# PunktSchweiss_ohne_NT2.net
KiCad netlist of a schematic drawn in EAGLE
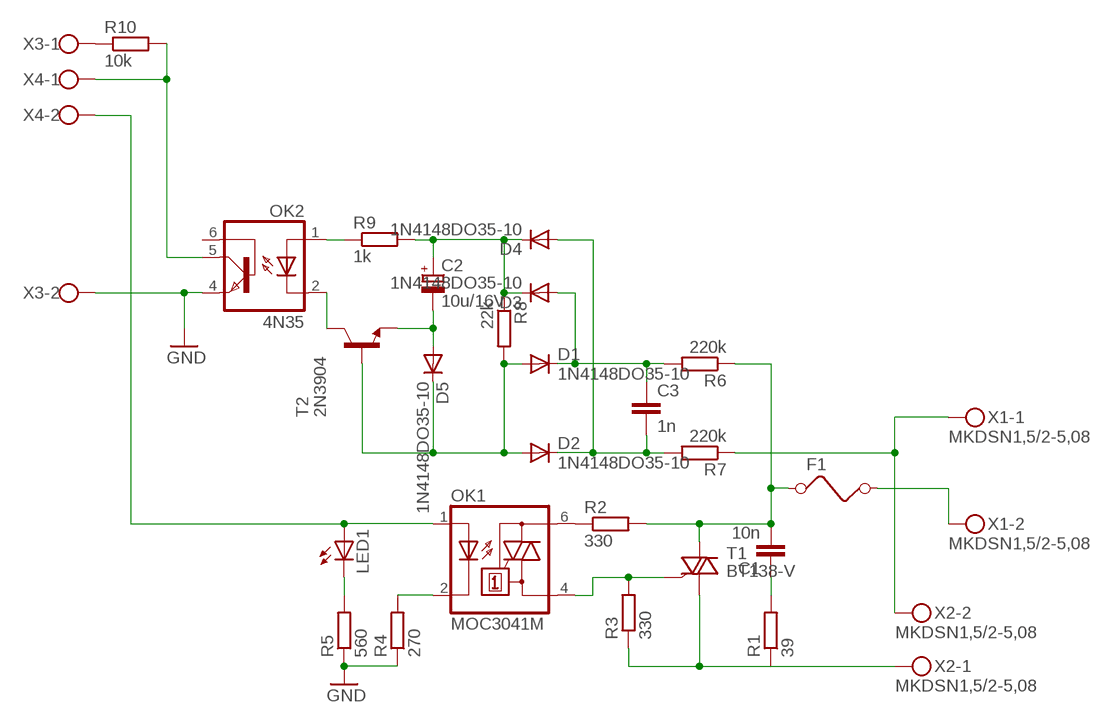
[diagram p0: schematic, sheet 1]

(export (version "E")
  (design (tool "Eeschema 10.0.6"))
  (components
    (comp (ref "C1")
      (value "10n")
      (footprint "eagle-import:C102-043X133")
      (libsource (lib "eagle-import") (part "C-EU102-043X133"))
    )
    (comp (ref "C2")
      (value "10u/16V")
      (footprint "eagle-import:E1,8-4")
      (libsource (lib "eagle-import") (part "CPOL-EUE1.8-4"))
    )
    (comp (ref "C3")
      (value "1n")
      (footprint "eagle-import:C050-030X075")
      (libsource (lib "eagle-import") (part "C-EU050-030X075"))
    )
    (comp (ref "D1")
      (value "1N4148DO35-10")
      (footprint "eagle-import:DO35-10")
      (libsource (lib "eagle-import") (part "1N4148DO35-10"))
    )
    (comp (ref "D2")
      (value "1N4148DO35-10")
      (footprint "eagle-import:DO35-10")
      (libsource (lib "eagle-import") (part "1N4148DO35-10"))
    )
    (comp (ref "D3")
      (value "1N4148DO35-10")
      (footprint "eagle-import:DO35-10")
      (libsource (lib "eagle-import") (part "1N4148DO35-10"))
    )
    (comp (ref "D4")
      (value "1N4148DO35-10")
      (footprint "eagle-import:DO35-10")
      (libsource (lib "eagle-import") (part "1N4148DO35-10"))
    )
    (comp (ref "D5")
      (value "1N4148DO35-10")
      (footprint "eagle-import:DO35-10")
      (libsource (lib "eagle-import") (part "1N4148DO35-10"))
    )
    (comp (ref "F1")
      (value "FUSE")
      (footprint "eagle-import:FUSE")
      (libsource (lib "eagle-import") (part "FUSE"))
    )
    (comp (ref "LED1")
      (value "LED3MM")
      (footprint "eagle-import:LED3MM")
      (libsource (lib "eagle-import") (part "LED3MM"))
    )
    (comp (ref "OK1")
      (value "MOC3041M")
      (footprint "eagle-import:DIL06")
      (fields (field (name "MF") "FAIRCHILD SEMICONDUCTOR"))
      (libsource (lib "eagle-import") (part "MOC3041M"))
    )
    (comp (ref "OK2")
      (value "4N35")
      (footprint "eagle-import:DIL06")
      (fields (field (name "MF") "FAIRCHILD SEMICONDUCTOR"))
      (libsource (lib "eagle-import") (part "4N35"))
    )
    (comp (ref "R1")
      (value "39")
      (footprint "eagle-import:0207_10")
      (libsource (lib "eagle-import") (part "R-EU_0207/10"))
    )
    (comp (ref "R2")
      (value "330")
      (footprint "eagle-import:0207_10")
      (libsource (lib "eagle-import") (part "R-EU_0207/10"))
    )
    (comp (ref "R3")
      (value "330")
      (footprint "eagle-import:0207_10")
      (libsource (lib "eagle-import") (part "R-EU_0207/10"))
    )
    (comp (ref "R4")
      (value "270")
      (footprint "eagle-import:0207_10")
      (libsource (lib "eagle-import") (part "R-EU_0207/10"))
    )
    (comp (ref "R5")
      (value "560")
      (footprint "eagle-import:0207_10")
      (libsource (lib "eagle-import") (part "R-EU_0207/10"))
    )
    (comp (ref "R6")
      (value "220k")
      (footprint "eagle-import:0207_10")
      (libsource (lib "eagle-import") (part "R-EU_0207/10"))
    )
    (comp (ref "R7")
      (value "220k")
      (footprint "eagle-import:0207_10")
      (libsource (lib "eagle-import") (part "R-EU_0207/10"))
    )
    (comp (ref "R8")
      (value "22k")
      (footprint "eagle-import:0207_10")
      (libsource (lib "eagle-import") (part "R-EU_0207/10"))
    )
    (comp (ref "R9")
      (value "1k")
      (footprint "eagle-import:0207_10")
      (libsource (lib "eagle-import") (part "R-EU_0207/10"))
    )
    (comp (ref "R10")
      (value "10k")
      (footprint "eagle-import:0207_10")
      (libsource (lib "eagle-import") (part "R-EU_0207/10"))
    )
    (comp (ref "T1")
      (value "BT138-V")
      (footprint "eagle-import:TO220BV")
      (libsource (lib "eagle-import") (part "BT138-V"))
    )
    (comp (ref "T2")
      (value "2N3904")
      (footprint "eagle-import:TO92")
      (libsource (lib "eagle-import") (part "2N3904"))
    )
    (comp (ref "X1")
      (value "MKDSN1,5/2-5,08")
      (footprint "eagle-import:MKDSN1,5_2-5,08")
      (fields (field (name "MPN") "MKDSN 1,5/2-5.08"))
      (libsource (lib "eagle-import") (part "MKDSN1,5/2-5,08"))
    )
    (comp (ref "X2")
      (value "MKDSN1,5/2-5,08")
      (footprint "eagle-import:MKDSN1,5_2-5,08")
      (fields (field (name "MPN") "MKDSN 1,5/2-5.08"))
      (libsource (lib "eagle-import") (part "MKDSN1,5/2-5,08"))
    )
    (comp (ref "X3")
      (value "W237-102")
      (footprint "eagle-import:W237-102")
      (fields (field (name "MPN") "237-102"))
      (libsource (lib "eagle-import") (part "W237-102"))
    )
    (comp (ref "X4")
      (value "W237-102")
      (footprint "eagle-import:W237-102")
      (fields (field (name "MPN") "237-102"))
      (libsource (lib "eagle-import") (part "W237-102"))
    )
  )
  (nets
    (net (code "1") (name "GND") (class "Default")
      (node (ref "OK2") (pin "4") (pinfunction "EMI_4") (pintype "passive"))
      (node (ref "R4") (pin "1") (pinfunction "1_1") (pintype "passive"))
      (node (ref "R5") (pin "1") (pinfunction "1_1") (pintype "passive"))
      (node (ref "X3") (pin "2") (pinfunction "KL_2") (pintype "passive"))
    )
    (net (code "2") (name "Net-(C1-Pad1)") (class "Default")
      (node (ref "C1") (pin "1") (pinfunction "1_1") (pintype "passive"))
      (node (ref "R1") (pin "2") (pinfunction "2_2") (pintype "passive"))
    )
    (net (code "3") (name "Net-(C2-Pad+)") (class "Default")
      (node (ref "C2") (pin "+") (pinfunction "+_+") (pintype "passive"))
      (node (ref "D3") (pin "C") (pinfunction "C_C") (pintype "passive"))
      (node (ref "D4") (pin "C") (pinfunction "C_C") (pintype "passive"))
      (node (ref "R8") (pin "1") (pinfunction "1_1") (pintype "passive"))
      (node (ref "R9") (pin "2") (pinfunction "2_2") (pintype "passive"))
    )
    (net (code "4") (name "Net-(C3-Pad1)") (class "Default")
      (node (ref "C3") (pin "1") (pinfunction "1_1") (pintype "passive"))
      (node (ref "D1") (pin "C") (pinfunction "C_C") (pintype "passive"))
      (node (ref "D3") (pin "A") (pinfunction "A_A") (pintype "passive"))
      (node (ref "R6") (pin "2") (pinfunction "2_2") (pintype "passive"))
    )
    (net (code "5") (name "Net-(C3-Pad2)") (class "Default")
      (node (ref "C3") (pin "2") (pinfunction "2_2") (pintype "passive"))
      (node (ref "D2") (pin "C") (pinfunction "C_C") (pintype "passive"))
      (node (ref "D4") (pin "A") (pinfunction "A_A") (pintype "passive"))
      (node (ref "R7") (pin "2") (pinfunction "2_2") (pintype "passive"))
    )
    (net (code "6") (name "Net-(LED1-C)") (class "Default")
      (node (ref "LED1") (pin "K") (pinfunction "C_K") (pintype "passive"))
      (node (ref "R5") (pin "2") (pinfunction "2_2") (pintype "passive"))
    )
    (net (code "7") (name "Net-(OK1-A)") (class "Default")
      (node (ref "LED1") (pin "A") (pinfunction "A_A") (pintype "passive"))
      (node (ref "OK1") (pin "1") (pinfunction "A_1") (pintype "passive"))
      (node (ref "X4") (pin "2") (pinfunction "KL_2") (pintype "passive"))
    )
    (net (code "8") (name "Net-(OK1-A1)") (class "Default")
      (node (ref "OK1") (pin "4") (pinfunction "A1_4") (pintype "passive"))
      (node (ref "R3") (pin "2") (pinfunction "2_2") (pintype "passive"))
      (node (ref "T1") (pin "G") (pinfunction "G_G") (pintype "passive"))
    )
    (net (code "9") (name "Net-(OK1-A2)") (class "Default")
      (node (ref "OK1") (pin "6") (pinfunction "A2_6") (pintype "passive"))
      (node (ref "R2") (pin "1") (pinfunction "1_1") (pintype "passive"))
    )
    (net (code "10") (name "Net-(OK1-C)") (class "Default")
      (node (ref "OK1") (pin "2") (pinfunction "C_2") (pintype "passive"))
      (node (ref "R4") (pin "2") (pinfunction "2_2") (pintype "passive"))
    )
    (net (code "11") (name "Net-(OK2-A)") (class "Default")
      (node (ref "OK2") (pin "1") (pinfunction "A_1") (pintype "passive"))
      (node (ref "R9") (pin "1") (pinfunction "1_1") (pintype "passive"))
    )
    (net (code "12") (name "Net-(OK2-C)") (class "Default")
      (node (ref "OK2") (pin "2") (pinfunction "C_2") (pintype "passive"))
      (node (ref "T2") (pin "1") (pinfunction "C_1") (pintype "passive"))
    )
    (net (code "13") (name "Net-(OK2-COL)") (class "Default")
      (node (ref "OK2") (pin "5") (pinfunction "COL_5") (pintype "passive"))
      (node (ref "R10") (pin "2") (pinfunction "2_2") (pintype "passive"))
      (node (ref "X4") (pin "1") (pinfunction "KL_1") (pintype "passive"))
    )
    (net (code "14") (name "Net-(T1-A1)") (class "Default")
      (node (ref "R1") (pin "1") (pinfunction "1_1") (pintype "passive"))
      (node (ref "R3") (pin "1") (pinfunction "1_1") (pintype "passive"))
      (node (ref "T1") (pin "T1") (pinfunction "A1_T1") (pintype "passive"))
      (node (ref "X2") (pin "1") (pinfunction "KL_1") (pintype "passive"))
    )
    (net (code "15") (name "Net-(T1-A2)") (class "Default")
      (node (ref "C1") (pin "2") (pinfunction "2_2") (pintype "passive"))
      (node (ref "F1") (pin "1") (pinfunction "1_1") (pintype "passive"))
      (node (ref "R2") (pin "2") (pinfunction "2_2") (pintype "passive"))
      (node (ref "R6") (pin "1") (pinfunction "1_1") (pintype "passive"))
      (node (ref "T1") (pin "T2") (pinfunction "A2_T2") (pintype "passive"))
    )
    (net (code "16") (name "Net-(T2-B)") (class "Default")
      (node (ref "D1") (pin "A") (pinfunction "A_A") (pintype "passive"))
      (node (ref "D2") (pin "A") (pinfunction "A_A") (pintype "passive"))
      (node (ref "D5") (pin "C") (pinfunction "C_C") (pintype "passive"))
      (node (ref "R8") (pin "2") (pinfunction "2_2") (pintype "passive"))
      (node (ref "T2") (pin "2") (pinfunction "B_2") (pintype "passive"))
    )
    (net (code "17") (name "Net-(T2-E)") (class "Default")
      (node (ref "C2") (pin "-") (pinfunction "-_-") (pintype "passive"))
      (node (ref "D5") (pin "A") (pinfunction "A_A") (pintype "passive"))
      (node (ref "T2") (pin "3") (pinfunction "E_3") (pintype "passive"))
    )
    (net (code "18") (name "Net-(X1A-KL)") (class "Default")
      (node (ref "R7") (pin "1") (pinfunction "1_1") (pintype "passive"))
      (node (ref "X1") (pin "1") (pinfunction "KL_1") (pintype "passive"))
      (node (ref "X2") (pin "2") (pinfunction "KL_2") (pintype "passive"))
    )
    (net (code "19") (name "Net-(X1B-KL)") (class "Default")
      (node (ref "F1") (pin "2") (pinfunction "2_2") (pintype "passive"))
      (node (ref "X1") (pin "2") (pinfunction "KL_2") (pintype "passive"))
    )
    (net (code "20") (name "Net-(X3A-KL)") (class "Default")
      (node (ref "R10") (pin "1") (pinfunction "1_1") (pintype "passive"))
      (node (ref "X3") (pin "1") (pinfunction "KL_1") (pintype "passive"))
    )
    (net (code "21") (name "unconnected-(OK2-BAS-Pad6)") (class "Default")
      (node (ref "OK2") (pin "6") (pinfunction "BAS_6") (pintype "passive"))
    )
  )
)
